# untitled.net
KiCad netlist of a schematic drawn in EAGLE
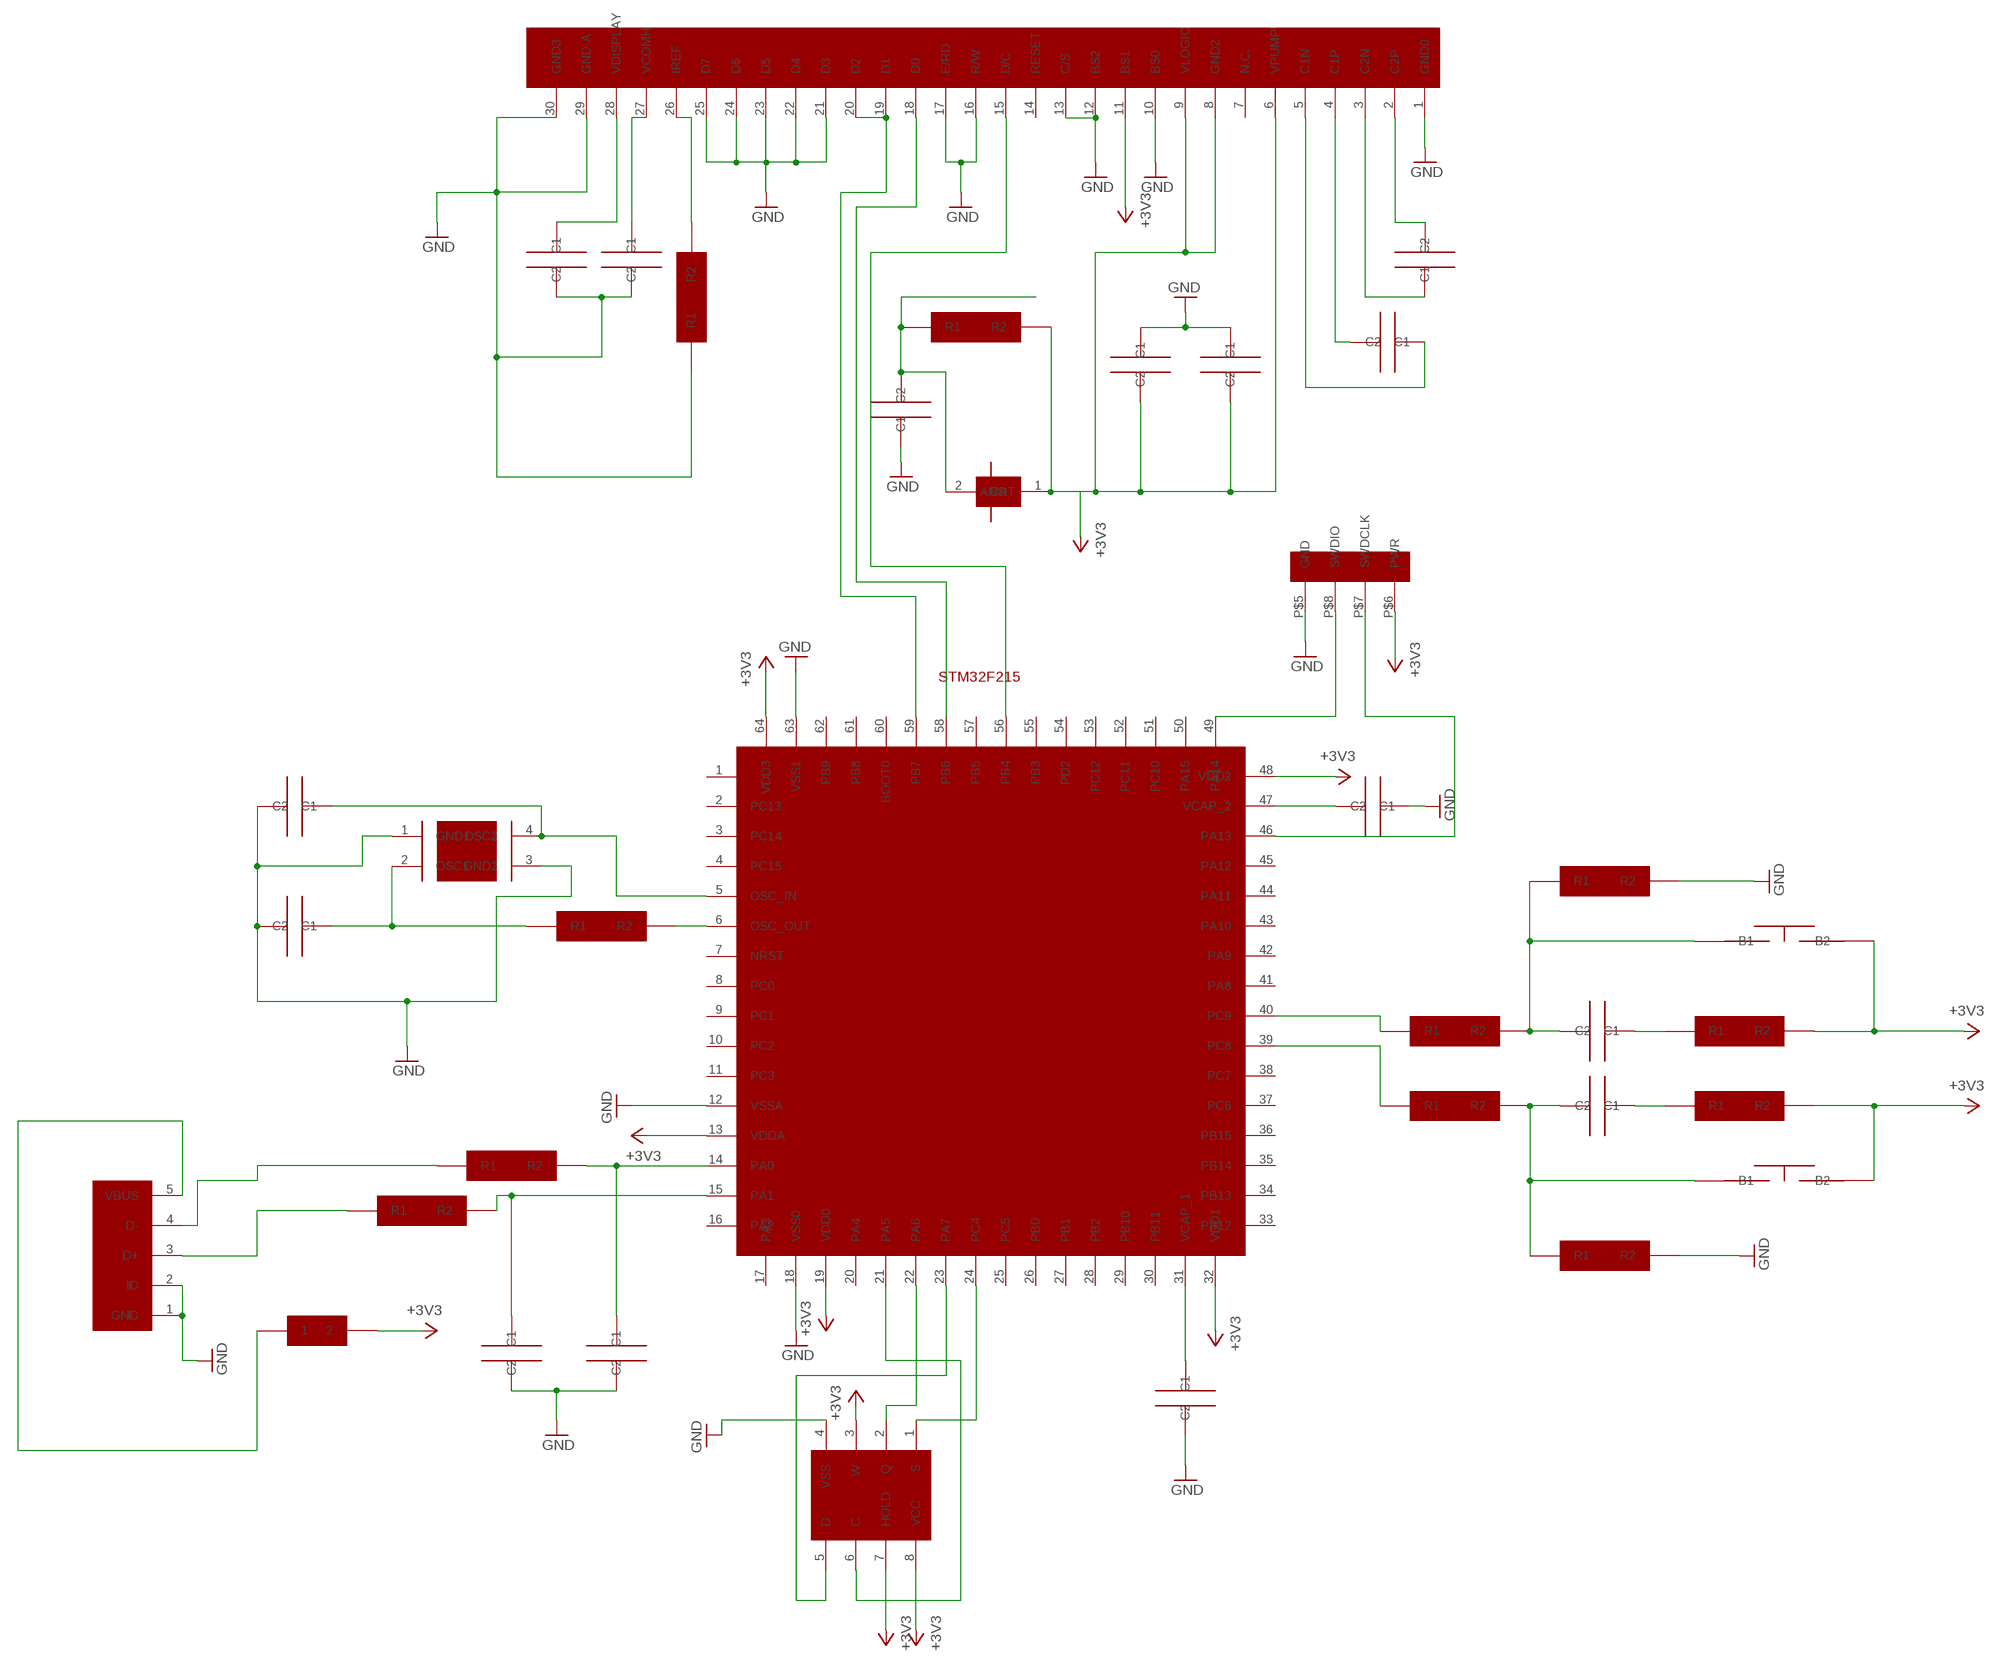
[diagram p0: schematic, sheet 1]

(export (version "E")
  (design (tool "Eeschema 10.0.6"))
  (components
    (comp (ref "C10")
      (value "100нф")
      (footprint "eagle-import:0805")
      (libsource (lib "eagle-import") (part "C0805"))
    )
    (comp (ref "C11")
      (value "100нф")
      (footprint "eagle-import:0805")
      (libsource (lib "eagle-import") (part "C0805"))
    )
    (comp (ref "C28")
      (value "8пф")
      (footprint "eagle-import:0805")
      (libsource (lib "eagle-import") (part "C0805"))
    )
    (comp (ref "C29")
      (value "8пф")
      (footprint "eagle-import:0805")
      (libsource (lib "eagle-import") (part "C0805"))
    )
    (comp (ref "C30")
      (value "47пф")
      (footprint "eagle-import:0805")
      (libsource (lib "eagle-import") (part "C0805"))
    )
    (comp (ref "C31")
      (value "47пф")
      (footprint "eagle-import:0805")
      (libsource (lib "eagle-import") (part "C0805"))
    )
    (comp (ref "C36")
      (value "2.2мкф")
      (footprint "eagle-import:0805")
      (libsource (lib "eagle-import") (part "C0805"))
    )
    (comp (ref "C37")
      (value "2.2мкф")
      (footprint "eagle-import:0805")
      (libsource (lib "eagle-import") (part "C0805"))
    )
    (comp (ref "C39")
      (value "1мкф")
      (footprint "eagle-import:0805")
      (libsource (lib "eagle-import") (part "C0805"))
    )
    (comp (ref "C40")
      (value "1мкф")
      (footprint "eagle-import:0805")
      (libsource (lib "eagle-import") (part "C0805"))
    )
    (comp (ref "C41")
      (value "1мкф")
      (footprint "eagle-import:0805")
      (libsource (lib "eagle-import") (part "C0805"))
    )
    (comp (ref "C42")
      (value "1мкф")
      (footprint "eagle-import:0805")
      (libsource (lib "eagle-import") (part "C0805"))
    )
    (comp (ref "C44")
      (value "4.7мкф")
      (footprint "eagle-import:0805")
      (libsource (lib "eagle-import") (part "C0805"))
    )
    (comp (ref "C46")
      (value "2.2мкф")
      (footprint "eagle-import:0805")
      (libsource (lib "eagle-import") (part "C0805"))
    )
    (comp (ref "C47")
      (value "4.7мкф")
      (footprint "eagle-import:0805")
      (libsource (lib "eagle-import") (part "C0805"))
    )
    (comp (ref "R2")
      (value "330")
      (footprint "eagle-import:0805")
      (libsource (lib "eagle-import") (part "R0805"))
    )
    (comp (ref "R3")
      (value "330")
      (footprint "eagle-import:0805")
      (libsource (lib "eagle-import") (part "R0805"))
    )
    (comp (ref "R6")
      (value "100")
      (footprint "eagle-import:0805")
      (libsource (lib "eagle-import") (part "R0805"))
    )
    (comp (ref "R7")
      (value "100")
      (footprint "eagle-import:0805")
      (libsource (lib "eagle-import") (part "R0805"))
    )
    (comp (ref "R14")
      (value "220k")
      (footprint "eagle-import:0805")
      (libsource (lib "eagle-import") (part "R0805"))
    )
    (comp (ref "R15")
      (value "220k")
      (footprint "eagle-import:0805")
      (libsource (lib "eagle-import") (part "R0805"))
    )
    (comp (ref "R32")
      (value "820")
      (footprint "eagle-import:0805")
      (libsource (lib "eagle-import") (part "R0805"))
    )
    (comp (ref "R33")
      (value "22")
      (footprint "eagle-import:0805")
      (libsource (lib "eagle-import") (part "R0805"))
    )
    (comp (ref "R34")
      (value "22")
      (footprint "eagle-import:0805")
      (libsource (lib "eagle-import") (part "R0805"))
    )
    (comp (ref "R43")
      (value "4.7к")
      (footprint "eagle-import:0805")
      (libsource (lib "eagle-import") (part "R0805"))
    )
    (comp (ref "R48")
      (value "910к")
      (footprint "eagle-import:0805")
      (libsource (lib "eagle-import") (part "R0805"))
    )
    (comp (ref "U$1")
      (value "STM32F215RE")
      (footprint "eagle-import:QFP64")
      (libsource (lib "eagle-import") (part "STM32F215RE"))
    )
    (comp (ref "U$18")
      (value "BUTTON")
      (footprint "eagle-import:BUTTON")
      (libsource (lib "eagle-import") (part "BUTTON"))
    )
    (comp (ref "U$19")
      (value "BUTTON")
      (footprint "eagle-import:BUTTON")
      (libsource (lib "eagle-import") (part "BUTTON"))
    )
    (comp (ref "U$26")
      (value "NX2520SA")
      (footprint "eagle-import:NX2520SA")
      (libsource (lib "eagle-import") (part "NX2520SA"))
    )
    (comp (ref "U$27")
      (value "MEMORYMEMORY2")
      (footprint "eagle-import:SOIC127P600X175-8N")
      (libsource (lib "eagle-import") (part "MEMORYMEMORY2"))
    )
    (comp (ref "U$35")
      (value "STABILITRON_3.3VSTABILITRON_SMD")
      (footprint "eagle-import:DIOC3314X145N")
      (libsource (lib "eagle-import") (part "STABILITRON_3.3VSTABILITRON_SMD"))
    )
    (comp (ref "U$38")
      (value "SSD1306")
      (footprint "eagle-import:SSD1306")
      (libsource (lib "eagle-import") (part "SSD1306"))
    )
    (comp (ref "U$45")
      (value "ESD")
      (footprint "eagle-import:ESD")
      (libsource (lib "eagle-import") (part "ESD"))
    )
    (comp (ref "U$49")
      (value "SWD")
      (footprint "eagle-import:SWD")
      (libsource (lib "eagle-import") (part "SWD"))
    )
    (comp (ref "U$50")
      (value "USB")
      (footprint "eagle-import:USB")
      (libsource (lib "eagle-import") (part "USB"))
    )
  )
  (nets
    (net (code "1") (name "+3V3") (class "Default")
      (node (ref "C41") (pin "1") (pinfunction "C1_1") (pintype "bidirectional"))
      (node (ref "C42") (pin "1") (pinfunction "C1_1") (pintype "bidirectional"))
      (node (ref "R43") (pin "2") (pinfunction "R2_2") (pintype "bidirectional"))
      (node (ref "R6") (pin "2") (pinfunction "R2_2") (pintype "bidirectional"))
      (node (ref "R7") (pin "2") (pinfunction "R2_2") (pintype "bidirectional"))
      (node (ref "U$1") (pin "13") (pinfunction "VDDA_13") (pintype "bidirectional"))
      (node (ref "U$1") (pin "19") (pinfunction "VDD0_19") (pintype "bidirectional"))
      (node (ref "U$1") (pin "32") (pinfunction "VDD1_32") (pintype "power_in"))
      (node (ref "U$1") (pin "48") (pinfunction "VDD2_48") (pintype "bidirectional"))
      (node (ref "U$1") (pin "64") (pinfunction "VDD3_64") (pintype "bidirectional"))
      (node (ref "U$18") (pin "2") (pinfunction "B2_2") (pintype "bidirectional"))
      (node (ref "U$19") (pin "2") (pinfunction "B2_2") (pintype "bidirectional"))
      (node (ref "U$27") (pin "3") (pinfunction "W_3") (pintype "bidirectional"))
      (node (ref "U$27") (pin "7") (pinfunction "HOLD_7") (pintype "bidirectional"))
      (node (ref "U$27") (pin "8") (pinfunction "VCC_8") (pintype "bidirectional"))
      (node (ref "U$35") (pin "2") (pinfunction "2_2") (pintype "bidirectional"))
      (node (ref "U$38") (pin "11") (pinfunction "BS1_11") (pintype "bidirectional"))
      (node (ref "U$38") (pin "6") (pinfunction "VPUMP_6") (pintype "bidirectional"))
      (node (ref "U$38") (pin "8") (pinfunction "GND2_8") (pintype "bidirectional"))
      (node (ref "U$38") (pin "9") (pinfunction "VLOGIC_9") (pintype "bidirectional"))
      (node (ref "U$45") (pin "1") (pinfunction "ANO_1") (pintype "bidirectional"))
      (node (ref "U$49") (pin "P$6") (pinfunction "PWR_P$6") (pintype "bidirectional"))
    )
    (net (code "2") (name "/VBAT") (class "Default")
      (node (ref "U$1") (pin "1") (pinfunction "VBAT_1") (pintype "power_in"))
    )
    (net (code "3") (name "GND") (class "Default")
      (node (ref "C28") (pin "1") (pinfunction "C1_1") (pintype "bidirectional"))
      (node (ref "C29") (pin "1") (pinfunction "C1_1") (pintype "bidirectional"))
      (node (ref "C30") (pin "1") (pinfunction "C1_1") (pintype "bidirectional"))
      (node (ref "C31") (pin "1") (pinfunction "C1_1") (pintype "bidirectional"))
      (node (ref "C36") (pin "1") (pinfunction "C1_1") (pintype "bidirectional"))
      (node (ref "C37") (pin "2") (pinfunction "C2_2") (pintype "bidirectional"))
      (node (ref "C41") (pin "2") (pinfunction "C2_2") (pintype "bidirectional"))
      (node (ref "C42") (pin "2") (pinfunction "C2_2") (pintype "bidirectional"))
      (node (ref "C44") (pin "2") (pinfunction "C2_2") (pintype "bidirectional"))
      (node (ref "C46") (pin "1") (pinfunction "C1_1") (pintype "bidirectional"))
      (node (ref "C47") (pin "1") (pinfunction "C1_1") (pintype "bidirectional"))
      (node (ref "R14") (pin "2") (pinfunction "R2_2") (pintype "bidirectional"))
      (node (ref "R15") (pin "2") (pinfunction "R2_2") (pintype "bidirectional"))
      (node (ref "R48") (pin "1") (pinfunction "R1_1") (pintype "bidirectional"))
      (node (ref "U$1") (pin "12") (pinfunction "VSSA_12") (pintype "bidirectional"))
      (node (ref "U$1") (pin "18") (pinfunction "VSS0_18") (pintype "bidirectional"))
      (node (ref "U$1") (pin "63") (pinfunction "VSS1_63") (pintype "bidirectional"))
      (node (ref "U$26") (pin "1") (pinfunction "GND1_1") (pintype "bidirectional"))
      (node (ref "U$26") (pin "3") (pinfunction "GND2_3") (pintype "bidirectional"))
      (node (ref "U$27") (pin "4") (pinfunction "VSS_4") (pintype "bidirectional"))
      (node (ref "U$38") (pin "1") (pinfunction "GND0_1") (pintype "bidirectional"))
      (node (ref "U$38") (pin "10") (pinfunction "BS0_10") (pintype "bidirectional"))
      (node (ref "U$38") (pin "12") (pinfunction "BS2_12") (pintype "bidirectional"))
      (node (ref "U$38") (pin "13") (pinfunction "C/S_13") (pintype "bidirectional"))
      (node (ref "U$38") (pin "16") (pinfunction "R/W_16") (pintype "bidirectional"))
      (node (ref "U$38") (pin "17") (pinfunction "E/RD_17") (pintype "bidirectional"))
      (node (ref "U$38") (pin "21") (pinfunction "D3_21") (pintype "bidirectional"))
      (node (ref "U$38") (pin "22") (pinfunction "D4_22") (pintype "bidirectional"))
      (node (ref "U$38") (pin "23") (pinfunction "D5_23") (pintype "bidirectional"))
      (node (ref "U$38") (pin "24") (pinfunction "D6_24") (pintype "bidirectional"))
      (node (ref "U$38") (pin "25") (pinfunction "D7_25") (pintype "bidirectional"))
      (node (ref "U$38") (pin "29") (pinfunction "GND-A_29") (pintype "bidirectional"))
      (node (ref "U$38") (pin "30") (pinfunction "GND3_30") (pintype "bidirectional"))
      (node (ref "U$49") (pin "P$5") (pinfunction "GND_P$5") (pintype "bidirectional"))
      (node (ref "U$50") (pin "1") (pinfunction "GND_1") (pintype "bidirectional"))
      (node (ref "U$50") (pin "2") (pinfunction "ID_2") (pintype "bidirectional"))
    )
    (net (code "4") (name "Net-(C10-C1)") (class "Default")
      (node (ref "C10") (pin "1") (pinfunction "C1_1") (pintype "bidirectional"))
      (node (ref "R14") (pin "1") (pinfunction "R1_1") (pintype "bidirectional"))
      (node (ref "R2") (pin "2") (pinfunction "R2_2") (pintype "bidirectional"))
      (node (ref "U$18") (pin "1") (pinfunction "B1_1") (pintype "bidirectional"))
    )
    (net (code "5") (name "Net-(C10-C2)") (class "Default")
      (node (ref "C10") (pin "2") (pinfunction "C2_2") (pintype "bidirectional"))
      (node (ref "R6") (pin "1") (pinfunction "R1_1") (pintype "bidirectional"))
    )
    (net (code "6") (name "Net-(C11-C1)") (class "Default")
      (node (ref "C11") (pin "1") (pinfunction "C1_1") (pintype "bidirectional"))
      (node (ref "R15") (pin "1") (pinfunction "R1_1") (pintype "bidirectional"))
      (node (ref "R3") (pin "2") (pinfunction "R2_2") (pintype "bidirectional"))
      (node (ref "U$19") (pin "1") (pinfunction "B1_1") (pintype "bidirectional"))
    )
    (net (code "7") (name "Net-(C11-C2)") (class "Default")
      (node (ref "C11") (pin "2") (pinfunction "C2_2") (pintype "bidirectional"))
      (node (ref "R7") (pin "1") (pinfunction "R1_1") (pintype "bidirectional"))
    )
    (net (code "8") (name "Net-(C28-C2)") (class "Default")
      (node (ref "C28") (pin "2") (pinfunction "C2_2") (pintype "bidirectional"))
      (node (ref "U$1") (pin "5") (pinfunction "OSC_IN_5") (pintype "input"))
      (node (ref "U$26") (pin "4") (pinfunction "OSC2_4") (pintype "bidirectional"))
    )
    (net (code "9") (name "Net-(C29-C2)") (class "Default")
      (node (ref "C29") (pin "2") (pinfunction "C2_2") (pintype "bidirectional"))
      (node (ref "R32") (pin "1") (pinfunction "R1_1") (pintype "bidirectional"))
      (node (ref "U$26") (pin "2") (pinfunction "OSC1_2") (pintype "bidirectional"))
    )
    (net (code "10") (name "Net-(C30-C2)") (class "Default")
      (node (ref "C30") (pin "2") (pinfunction "C2_2") (pintype "bidirectional"))
      (node (ref "R33") (pin "2") (pinfunction "R2_2") (pintype "bidirectional"))
      (node (ref "U$1") (pin "14") (pinfunction "PA0_14") (pintype "bidirectional"))
    )
    (net (code "11") (name "Net-(C31-C2)") (class "Default")
      (node (ref "C31") (pin "2") (pinfunction "C2_2") (pintype "bidirectional"))
      (node (ref "R34") (pin "2") (pinfunction "R2_2") (pintype "bidirectional"))
      (node (ref "U$1") (pin "15") (pinfunction "PA1_15") (pintype "bidirectional"))
    )
    (net (code "12") (name "Net-(C36-C2)") (class "Default")
      (node (ref "C36") (pin "2") (pinfunction "C2_2") (pintype "bidirectional"))
      (node (ref "U$1") (pin "31") (pinfunction "VCAP_1_31") (pintype "bidirectional"))
    )
    (net (code "13") (name "Net-(C37-C1)") (class "Default")
      (node (ref "C37") (pin "1") (pinfunction "C1_1") (pintype "bidirectional"))
      (node (ref "U$1") (pin "47") (pinfunction "VCAP_2_47") (pintype "bidirectional"))
    )
    (net (code "14") (name "Net-(C39-C1)") (class "Default")
      (node (ref "C39") (pin "1") (pinfunction "C1_1") (pintype "bidirectional"))
      (node (ref "U$38") (pin "2") (pinfunction "C2P_2") (pintype "bidirectional"))
    )
    (net (code "15") (name "Net-(C39-C2)") (class "Default")
      (node (ref "C39") (pin "2") (pinfunction "C2_2") (pintype "bidirectional"))
      (node (ref "U$38") (pin "3") (pinfunction "C2N_3") (pintype "bidirectional"))
    )
    (net (code "16") (name "Net-(C40-C1)") (class "Default")
      (node (ref "C40") (pin "1") (pinfunction "C1_1") (pintype "bidirectional"))
      (node (ref "U$38") (pin "4") (pinfunction "C1P_4") (pintype "bidirectional"))
    )
    (net (code "17") (name "Net-(C40-C2)") (class "Default")
      (node (ref "C40") (pin "2") (pinfunction "C2_2") (pintype "bidirectional"))
      (node (ref "U$38") (pin "5") (pinfunction "C1N_5") (pintype "bidirectional"))
    )
    (net (code "18") (name "Net-(C44-C1)") (class "Default")
      (node (ref "C44") (pin "1") (pinfunction "C1_1") (pintype "bidirectional"))
      (node (ref "R43") (pin "1") (pinfunction "R1_1") (pintype "bidirectional"))
      (node (ref "U$45") (pin "2") (pinfunction "CAT_2") (pintype "bidirectional"))
    )
    (net (code "19") (name "Net-(C46-C2)") (class "Default")
      (node (ref "C46") (pin "2") (pinfunction "C2_2") (pintype "bidirectional"))
      (node (ref "U$38") (pin "28") (pinfunction "VDISPLAY_28") (pintype "bidirectional"))
    )
    (net (code "20") (name "Net-(C47-C2)") (class "Default")
      (node (ref "C47") (pin "2") (pinfunction "C2_2") (pintype "bidirectional"))
      (node (ref "U$38") (pin "27") (pinfunction "VCOMH_27") (pintype "bidirectional"))
    )
    (net (code "21") (name "Net-(R2-R1)") (class "Default")
      (node (ref "R2") (pin "1") (pinfunction "R1_1") (pintype "bidirectional"))
      (node (ref "U$1") (pin "40") (pinfunction "PC9_40") (pintype "bidirectional"))
    )
    (net (code "22") (name "Net-(R3-R1)") (class "Default")
      (node (ref "R3") (pin "1") (pinfunction "R1_1") (pintype "bidirectional"))
      (node (ref "U$1") (pin "39") (pinfunction "PC8_39") (pintype "bidirectional"))
    )
    (net (code "23") (name "Net-(R32-R2)") (class "Default")
      (node (ref "R32") (pin "2") (pinfunction "R2_2") (pintype "bidirectional"))
      (node (ref "U$1") (pin "6") (pinfunction "OSC_OUT_6") (pintype "input"))
    )
    (net (code "24") (name "Net-(R33-R1)") (class "Default")
      (node (ref "R33") (pin "1") (pinfunction "R1_1") (pintype "bidirectional"))
      (node (ref "U$50") (pin "4") (pinfunction "D-_4") (pintype "bidirectional"))
    )
    (net (code "25") (name "Net-(R34-R1)") (class "Default")
      (node (ref "R34") (pin "1") (pinfunction "R1_1") (pintype "bidirectional"))
      (node (ref "U$50") (pin "3") (pinfunction "D+_3") (pintype "bidirectional"))
    )
    (net (code "26") (name "Net-(R48-R2)") (class "Default")
      (node (ref "R48") (pin "2") (pinfunction "R2_2") (pintype "bidirectional"))
      (node (ref "U$38") (pin "26") (pinfunction "IREF_26") (pintype "bidirectional"))
    )
    (net (code "27") (name "Net-(U$1-PA5)") (class "Default")
      (node (ref "U$1") (pin "21") (pinfunction "PA5_21") (pintype "bidirectional"))
      (node (ref "U$27") (pin "6") (pinfunction "C_6") (pintype "bidirectional"))
    )
    (net (code "28") (name "Net-(U$1-PA6)") (class "Default")
      (node (ref "U$1") (pin "22") (pinfunction "PA6_22") (pintype "bidirectional"))
      (node (ref "U$27") (pin "2") (pinfunction "Q_2") (pintype "bidirectional"))
    )
    (net (code "29") (name "Net-(U$1-PA7)") (class "Default")
      (node (ref "U$1") (pin "23") (pinfunction "PA7_23") (pintype "bidirectional"))
      (node (ref "U$27") (pin "5") (pinfunction "D_5") (pintype "bidirectional"))
    )
    (net (code "30") (name "Net-(U$1-PA13)") (class "Default")
      (node (ref "U$1") (pin "46") (pinfunction "PA13_46") (pintype "bidirectional"))
      (node (ref "U$49") (pin "P$7") (pinfunction "SWDCLK_P$7") (pintype "bidirectional"))
    )
    (net (code "31") (name "Net-(U$1-PA14)") (class "Default")
      (node (ref "U$1") (pin "49") (pinfunction "PA14_49") (pintype "bidirectional"))
      (node (ref "U$49") (pin "P$8") (pinfunction "SWDIO_P$8") (pintype "bidirectional"))
    )
    (net (code "32") (name "Net-(U$1-PB4)") (class "Default")
      (node (ref "U$1") (pin "56") (pinfunction "PB4_56") (pintype "bidirectional"))
      (node (ref "U$38") (pin "15") (pinfunction "D/C_15") (pintype "bidirectional"))
    )
    (net (code "33") (name "Net-(U$1-PB6)") (class "Default")
      (node (ref "U$1") (pin "58") (pinfunction "PB6_58") (pintype "bidirectional"))
      (node (ref "U$38") (pin "18") (pinfunction "D0_18") (pintype "bidirectional"))
    )
    (net (code "34") (name "Net-(U$1-PB7)") (class "Default")
      (node (ref "U$1") (pin "59") (pinfunction "PB7_59") (pintype "bidirectional"))
      (node (ref "U$38") (pin "19") (pinfunction "D1_19") (pintype "bidirectional"))
      (node (ref "U$38") (pin "20") (pinfunction "D2_20") (pintype "bidirectional"))
    )
    (net (code "35") (name "Net-(U$1-PC4)") (class "Default")
      (node (ref "U$1") (pin "24") (pinfunction "PC4_24") (pintype "bidirectional"))
      (node (ref "U$27") (pin "1") (pinfunction "S_1") (pintype "bidirectional"))
    )
    (net (code "36") (name "Net-(U$50-VBUS)") (class "Default")
      (node (ref "U$35") (pin "1") (pinfunction "1_1") (pintype "bidirectional"))
      (node (ref "U$50") (pin "5") (pinfunction "VBUS_5") (pintype "bidirectional"))
    )
    (net (code "37") (name "unconnected-(U$1-BOOT0-Pad60)") (class "Default")
      (node (ref "U$1") (pin "60") (pinfunction "BOOT0_60") (pintype "bidirectional"))
    )
    (net (code "38") (name "unconnected-(U$1-NRST-Pad7)") (class "Default")
      (node (ref "U$1") (pin "7") (pinfunction "NRST_7") (pintype "bidirectional"))
    )
    (net (code "39") (name "unconnected-(U$1-PA2-Pad16)") (class "Default")
      (node (ref "U$1") (pin "16") (pinfunction "PA2_16") (pintype "bidirectional"))
    )
    (net (code "40") (name "unconnected-(U$1-PA3-Pad17)") (class "Default")
      (node (ref "U$1") (pin "17") (pinfunction "PA3_17") (pintype "bidirectional"))
    )
    (net (code "41") (name "unconnected-(U$1-PA4-Pad20)") (class "Default")
      (node (ref "U$1") (pin "20") (pinfunction "PA4_20") (pintype "bidirectional"))
    )
    (net (code "42") (name "unconnected-(U$1-PA8-Pad41)") (class "Default")
      (node (ref "U$1") (pin "41") (pinfunction "PA8_41") (pintype "bidirectional"))
    )
    (net (code "43") (name "unconnected-(U$1-PA9-Pad42)") (class "Default")
      (node (ref "U$1") (pin "42") (pinfunction "PA9_42") (pintype "bidirectional"))
    )
    (net (code "44") (name "unconnected-(U$1-PA10-Pad43)") (class "Default")
      (node (ref "U$1") (pin "43") (pinfunction "PA10_43") (pintype "bidirectional"))
    )
    (net (code "45") (name "unconnected-(U$1-PA11-Pad44)") (class "Default")
      (node (ref "U$1") (pin "44") (pinfunction "PA11_44") (pintype "bidirectional"))
    )
    (net (code "46") (name "unconnected-(U$1-PA12-Pad45)") (class "Default")
      (node (ref "U$1") (pin "45") (pinfunction "PA12_45") (pintype "bidirectional"))
    )
    (net (code "47") (name "unconnected-(U$1-PA15-Pad50)") (class "Default")
      (node (ref "U$1") (pin "50") (pinfunction "PA15_50") (pintype "bidirectional"))
    )
    (net (code "48") (name "unconnected-(U$1-PB0-Pad26)") (class "Default")
      (node (ref "U$1") (pin "26") (pinfunction "PB0_26") (pintype "bidirectional"))
    )
    (net (code "49") (name "unconnected-(U$1-PB1-Pad27)") (class "Default")
      (node (ref "U$1") (pin "27") (pinfunction "PB1_27") (pintype "bidirectional"))
    )
    (net (code "50") (name "unconnected-(U$1-PB2-Pad28)") (class "Default")
      (node (ref "U$1") (pin "28") (pinfunction "PB2_28") (pintype "bidirectional"))
    )
    (net (code "51") (name "unconnected-(U$1-PB3-Pad55)") (class "Default")
      (node (ref "U$1") (pin "55") (pinfunction "PB3_55") (pintype "bidirectional"))
    )
    (net (code "52") (name "unconnected-(U$1-PB5-Pad57)") (class "Default")
      (node (ref "U$1") (pin "57") (pinfunction "PB5_57") (pintype "bidirectional"))
    )
    (net (code "53") (name "unconnected-(U$1-PB8-Pad61)") (class "Default")
      (node (ref "U$1") (pin "61") (pinfunction "PB8_61") (pintype "bidirectional"))
    )
    (net (code "54") (name "unconnected-(U$1-PB9-Pad62)") (class "Default")
      (node (ref "U$1") (pin "62") (pinfunction "PB9_62") (pintype "bidirectional"))
    )
    (net (code "55") (name "unconnected-(U$1-PB10-Pad29)") (class "Default")
      (node (ref "U$1") (pin "29") (pinfunction "PB10_29") (pintype "bidirectional"))
    )
    (net (code "56") (name "unconnected-(U$1-PB11-Pad30)") (class "Default")
      (node (ref "U$1") (pin "30") (pinfunction "PB11_30") (pintype "bidirectional"))
    )
    (net (code "57") (name "unconnected-(U$1-PB12-Pad33)") (class "Default")
      (node (ref "U$1") (pin "33") (pinfunction "PB12_33") (pintype "bidirectional"))
    )
    (net (code "58") (name "unconnected-(U$1-PB13-Pad34)") (class "Default")
      (node (ref "U$1") (pin "34") (pinfunction "PB13_34") (pintype "bidirectional"))
    )
    (net (code "59") (name "unconnected-(U$1-PB14-Pad35)") (class "Default")
      (node (ref "U$1") (pin "35") (pinfunction "PB14_35") (pintype "bidirectional"))
    )
    (net (code "60") (name "unconnected-(U$1-PB15-Pad36)") (class "Default")
      (node (ref "U$1") (pin "36") (pinfunction "PB15_36") (pintype "bidirectional"))
    )
    (net (code "61") (name "unconnected-(U$1-PC0-Pad8)") (class "Default")
      (node (ref "U$1") (pin "8") (pinfunction "PC0_8") (pintype "bidirectional"))
    )
    (net (code "62") (name "unconnected-(U$1-PC1-Pad9)") (class "Default")
      (node (ref "U$1") (pin "9") (pinfunction "PC1_9") (pintype "bidirectional"))
    )
    (net (code "63") (name "unconnected-(U$1-PC2-Pad10)") (class "Default")
      (node (ref "U$1") (pin "10") (pinfunction "PC2_10") (pintype "bidirectional"))
    )
    (net (code "64") (name "unconnected-(U$1-PC3-Pad11)") (class "Default")
      (node (ref "U$1") (pin "11") (pinfunction "PC3_11") (pintype "bidirectional"))
    )
    (net (code "65") (name "unconnected-(U$1-PC5-Pad25)") (class "Default")
      (node (ref "U$1") (pin "25") (pinfunction "PC5_25") (pintype "bidirectional"))
    )
    (net (code "66") (name "unconnected-(U$1-PC6-Pad37)") (class "Default")
      (node (ref "U$1") (pin "37") (pinfunction "PC6_37") (pintype "bidirectional"))
    )
    (net (code "67") (name "unconnected-(U$1-PC7-Pad38)") (class "Default")
      (node (ref "U$1") (pin "38") (pinfunction "PC7_38") (pintype "bidirectional"))
    )
    (net (code "68") (name "unconnected-(U$1-PC10-Pad51)") (class "Default")
      (node (ref "U$1") (pin "51") (pinfunction "PC10_51") (pintype "bidirectional"))
    )
    (net (code "69") (name "unconnected-(U$1-PC11-Pad52)") (class "Default")
      (node (ref "U$1") (pin "52") (pinfunction "PC11_52") (pintype "bidirectional"))
    )
    (net (code "70") (name "unconnected-(U$1-PC12-Pad53)") (class "Default")
      (node (ref "U$1") (pin "53") (pinfunction "PC12_53") (pintype "bidirectional"))
    )
    (net (code "71") (name "unconnected-(U$1-PC13-Pad2)") (class "Default")
      (node (ref "U$1") (pin "2") (pinfunction "PC13_2") (pintype "bidirectional"))
    )
    (net (code "72") (name "unconnected-(U$1-PC14-Pad3)") (class "Default")
      (node (ref "U$1") (pin "3") (pinfunction "PC14_3") (pintype "bidirectional"))
    )
    (net (code "73") (name "unconnected-(U$1-PC15-Pad4)") (class "Default")
      (node (ref "U$1") (pin "4") (pinfunction "PC15_4") (pintype "bidirectional"))
    )
    (net (code "74") (name "unconnected-(U$1-PD2-Pad54)") (class "Default")
      (node (ref "U$1") (pin "54") (pinfunction "PD2_54") (pintype "bidirectional"))
    )
    (net (code "75") (name "unconnected-(U$38-N.C.-Pad7)") (class "Default")
      (node (ref "U$38") (pin "7") (pinfunction "N.C._7") (pintype "bidirectional"))
    )
    (net (code "76") (name "unconnected-(U$38-RESET-Pad14)") (class "Default")
      (node (ref "U$38") (pin "14") (pinfunction "RESET_14") (pintype "bidirectional"))
    )
  )
)
